# ngp-main.net
KiCad netlist of a schematic drawn in Altium Designer
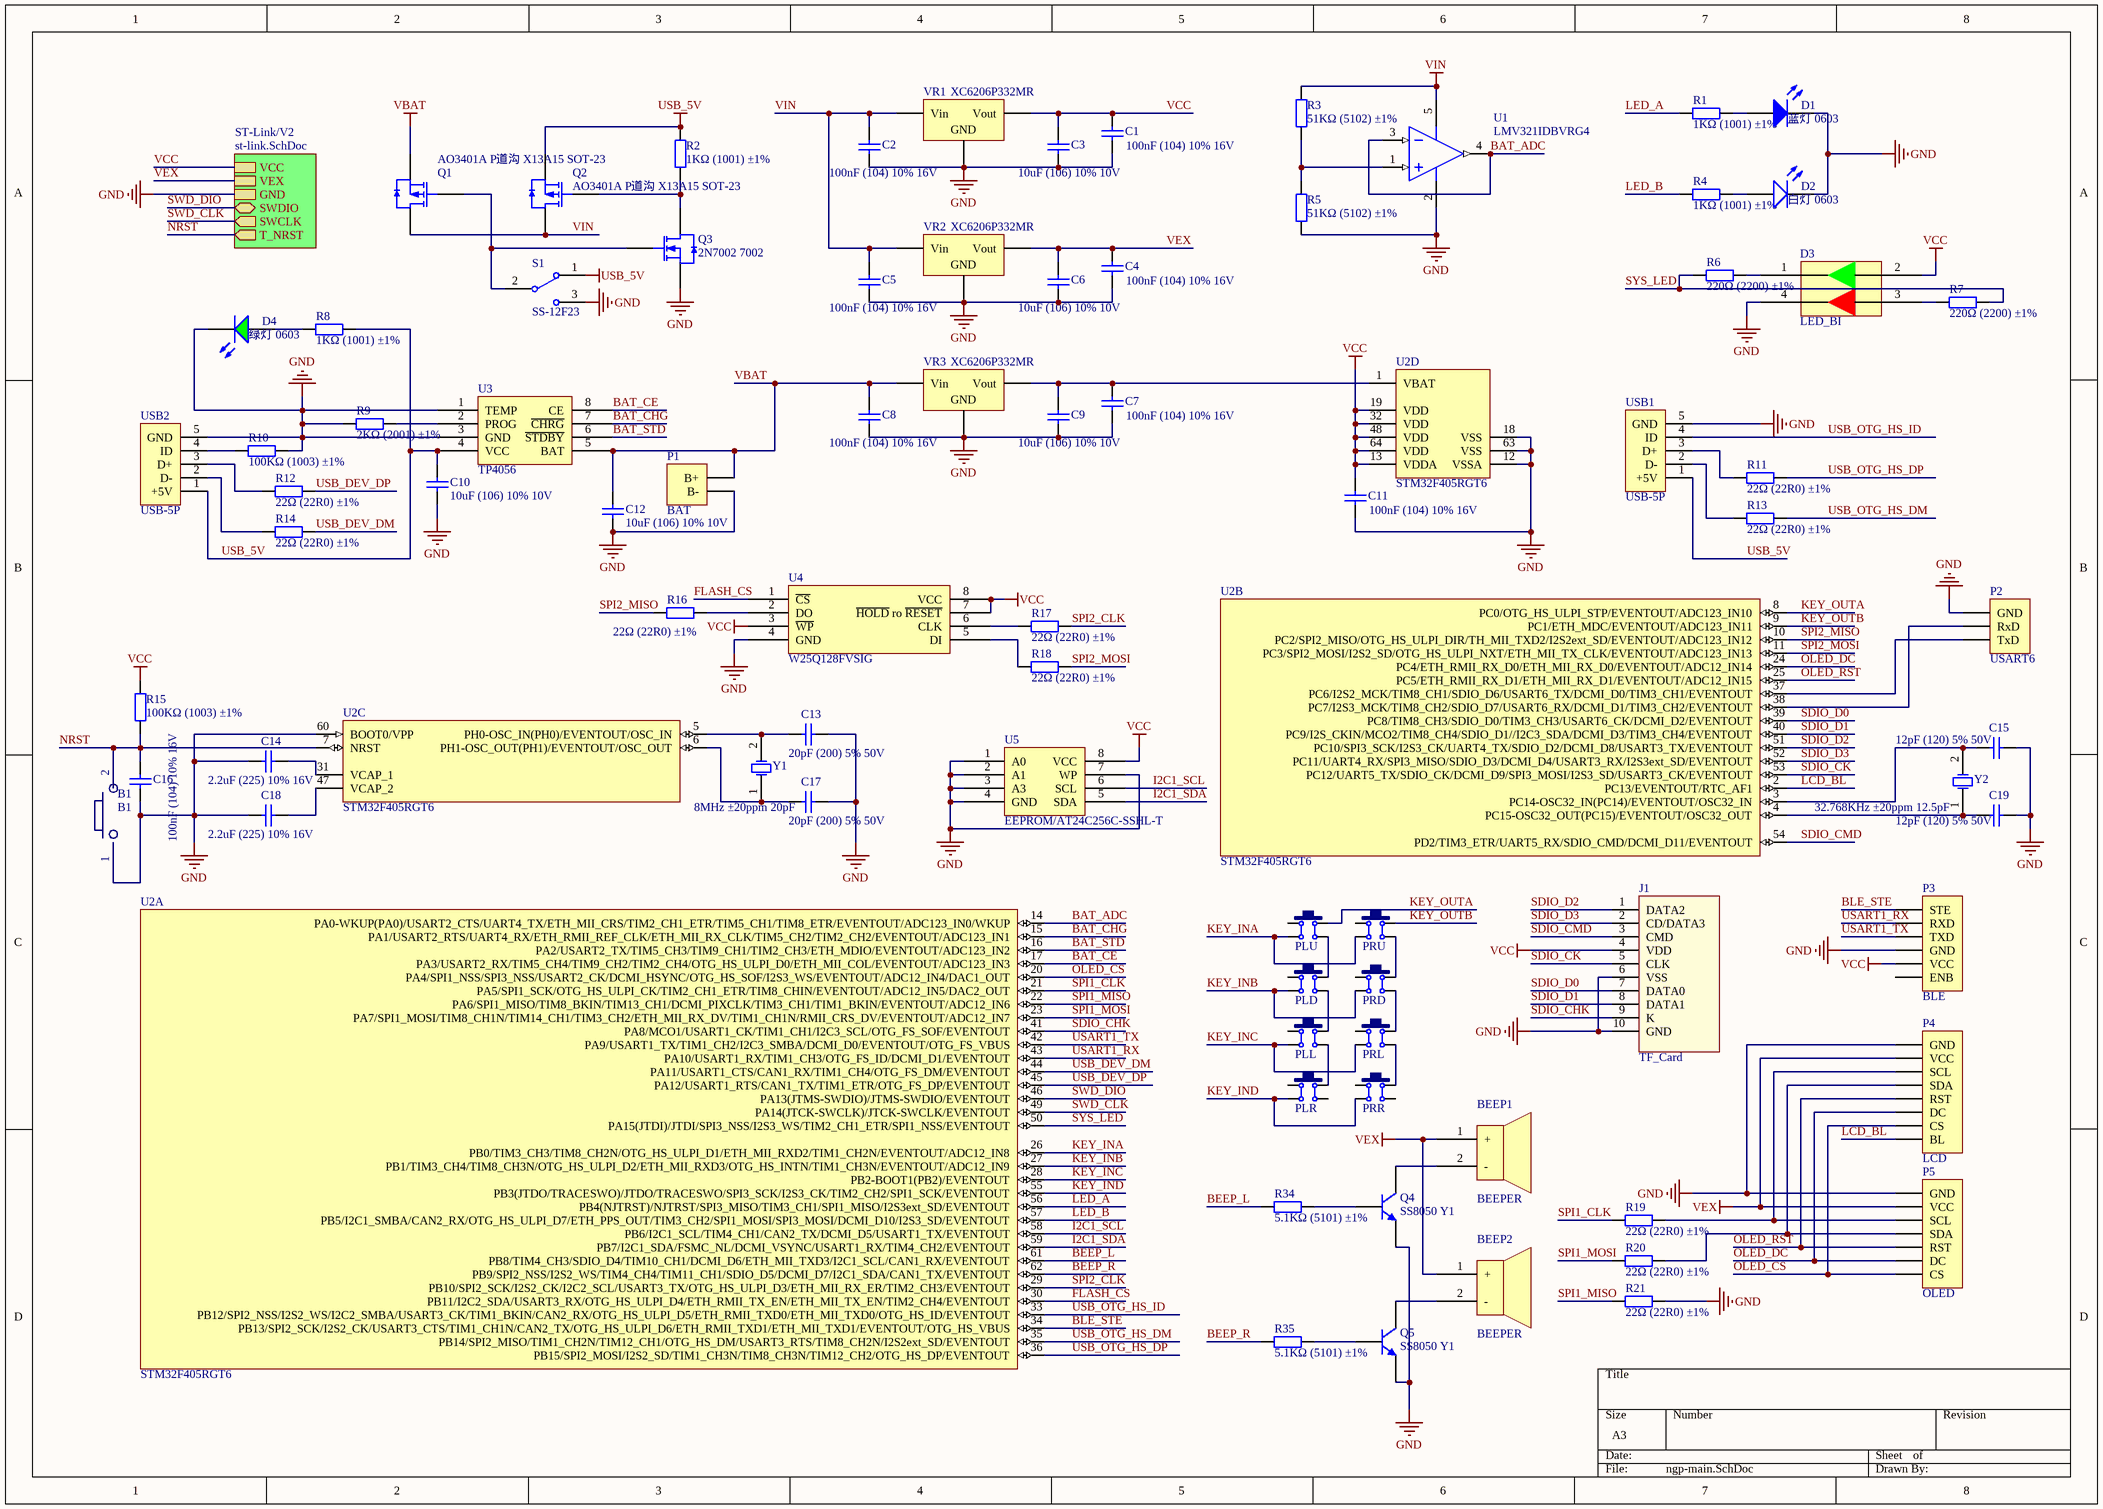
[diagram p0: ngp-main.SchDoc]

(export (version "E")
  (design (tool "Eeschema 10.0.6"))
  (components
    (comp (ref "B1")
      (value "B1")
      (footprint "MetalButton")
      (libsource (lib "MetalButton") (part "MetalButton"))
    )
    (comp (ref "BEEP1") (value "BEEPER") (footprint "BEEPER") (libsource (lib "ngv-main") (part "BEEPER")))
    (comp (ref "BEEP2") (value "BEEPER") (footprint "BEEPER") (libsource (lib "ngv-main") (part "BEEPER")))
    (comp (ref "C1")
      (value "100nF (104) 10% 16V")
      (footprint "0402_C")
      (description "贴片电容")
      (libsource (lib "Miscellaneous Devices LC") (part "0402 100nF (104) 10% 16V"))
    )
    (comp (ref "C2")
      (value "100nF (104) 10% 16V")
      (footprint "0402_C")
      (description "贴片电容")
      (libsource (lib "Miscellaneous Devices LC") (part "0402 100nF (104) 10% 16V"))
    )
    (comp (ref "C3")
      (value "10uF (106) 10% 10V")
      (footprint "0603_C")
      (description "贴片电容")
      (libsource (lib "Miscellaneous Devices LC") (part "0603 10uF (106) 10% 10V"))
    )
    (comp (ref "C4")
      (value "100nF (104) 10% 16V")
      (footprint "0402_C")
      (description "贴片电容")
      (libsource (lib "Miscellaneous Devices LC") (part "0402 100nF (104) 10% 16V"))
    )
    (comp (ref "C5")
      (value "100nF (104) 10% 16V")
      (footprint "0402_C")
      (description "贴片电容")
      (libsource (lib "Miscellaneous Devices LC") (part "0402 100nF (104) 10% 16V"))
    )
    (comp (ref "C6")
      (value "10uF (106) 10% 10V")
      (footprint "0603_C")
      (description "贴片电容")
      (libsource (lib "Miscellaneous Devices LC") (part "0603 10uF (106) 10% 10V"))
    )
    (comp (ref "C7")
      (value "100nF (104) 10% 16V")
      (footprint "0402_C")
      (description "贴片电容")
      (libsource (lib "Miscellaneous Devices LC") (part "0402 100nF (104) 10% 16V"))
    )
    (comp (ref "C8")
      (value "100nF (104) 10% 16V")
      (footprint "0402_C")
      (description "贴片电容")
      (libsource (lib "Miscellaneous Devices LC") (part "0402 100nF (104) 10% 16V"))
    )
    (comp (ref "C9")
      (value "10uF (106) 10% 10V")
      (footprint "0603_C")
      (description "贴片电容")
      (libsource (lib "Miscellaneous Devices LC") (part "0603 10uF (106) 10% 10V"))
    )
    (comp (ref "C10")
      (value "10uF (106) 10% 10V")
      (footprint "0603_C")
      (description "贴片电容")
      (libsource (lib "Miscellaneous Devices LC") (part "0603 10uF (106) 10% 10V"))
    )
    (comp (ref "C11")
      (value "100nF (104) 10% 16V")
      (footprint "0402_C")
      (description "贴片电容")
      (libsource (lib "Miscellaneous Devices LC") (part "0402 100nF (104) 10% 16V"))
    )
    (comp (ref "C12")
      (value "10uF (106) 10% 10V")
      (footprint "0603_C")
      (description "贴片电容")
      (libsource (lib "Miscellaneous Devices LC") (part "0603 10uF (106) 10% 10V"))
    )
    (comp (ref "C13")
      (value "20pF (200) 5% 50V")
      (footprint "0402_C")
      (description "贴片电容")
      (libsource (lib "Miscellaneous Devices LC") (part "0402 20pF (200) 5% 50V"))
    )
    (comp (ref "C14")
      (value "2.2uF (225) 10% 16V")
      (footprint "0603_C")
      (description "贴片电容")
      (libsource (lib "Miscellaneous Devices LC") (part "0603 2.2uF (225) 10% 16V"))
    )
    (comp (ref "C15")
      (value "12pF (120) 5% 50V")
      (footprint "0402_C")
      (description "贴片电容")
      (libsource (lib "Miscellaneous Devices LC") (part "0402 12pF (120) 5% 50V"))
    )
    (comp (ref "C16")
      (value "100nF (104) 10% 16V")
      (footprint "0402_C")
      (description "贴片电容")
      (libsource (lib "Miscellaneous Devices LC") (part "0402 100nF (104) 10% 16V"))
    )
    (comp (ref "C17")
      (value "20pF (200) 5% 50V")
      (footprint "0402_C")
      (description "贴片电容")
      (libsource (lib "Miscellaneous Devices LC") (part "0402 20pF (200) 5% 50V"))
    )
    (comp (ref "C18")
      (value "2.2uF (225) 10% 16V")
      (footprint "0603_C")
      (description "贴片电容")
      (libsource (lib "Miscellaneous Devices LC") (part "0603 2.2uF (225) 10% 16V"))
    )
    (comp (ref "C19")
      (value "12pF (120) 5% 50V")
      (footprint "0402_C")
      (description "贴片电容")
      (libsource (lib "Miscellaneous Devices LC") (part "0402 12pF (120) 5% 50V"))
    )
    (comp (ref "D1")
      (value "蓝灯 0603")
      (footprint "0603_LED_S1")
      (description "发光二极管")
      (libsource (lib "Miscellaneous Devices LC") (part "0603 蓝灯"))
    )
    (comp (ref "D2")
      (value "白灯 0603")
      (footprint "0603_LED_S1")
      (description "发光二极管")
      (libsource (lib "Miscellaneous Devices LC") (part "0603 白灯"))
    )
    (comp (ref "D3") (value "LED_BI") (footprint "LED_BI") (libsource (lib "ngv-ext") (part "LED_BI")))
    (comp (ref "D4")
      (value "绿灯 0603")
      (footprint "0603_LED_S1")
      (description "发光二极管")
      (libsource (lib "Miscellaneous Devices LC") (part "0603 绿灯"))
    )
    (comp (ref "J1")
      (value "TF_Card")
      (footprint "Micro SD")
      (description "TF卡座")
      (fields (field (name "版权归属") "源创客"))
      (libsource (lib "4.1   - 接口类") (part "TF_Card"))
    )
    (comp (ref "P1")
      (value "BAT")
      (footprint "HDR1X2")
      (description "Header, 2-Pin")
      (fields (field (name "PUBLISHER") "Altium Limited"))
      (libsource (lib "Miscellaneous Connectors") (part "Header 2"))
    )
    (comp (ref "P2")
      (value "USART6")
      (footprint "HDR1X3H")
      (description "Header, 3-Pin, Right Angle")
      (fields (field (name "PUBLISHER") "Altium Limited"))
      (libsource (lib "Miscellaneous Connectors") (part "Header 3H"))
    )
    (comp (ref "P3")
      (value "BLE")
      (footprint "HDR1X6")
      (description "Header, 6-Pin")
      (fields (field (name "PUBLISHER") "Altium Limited"))
      (libsource (lib "Miscellaneous Connectors") (part "Header 6"))
    )
    (comp (ref "P4")
      (value "LCD")
      (footprint "HDR1X8")
      (description "Header, 8-Pin")
      (fields (field (name "PUBLISHER") "Altium Limited"))
      (libsource (lib "Miscellaneous Connectors") (part "Header 8"))
    )
    (comp (ref "P5")
      (value "OLED")
      (footprint "HDR1X7")
      (description "Header, 7-Pin")
      (fields (field (name "PUBLISHER") "Altium Limited"))
      (libsource (lib "Miscellaneous Connectors") (part "Header 7"))
    )
    (comp (ref "PLD")
      (value "6x6x5")
      (footprint "TSW SMD-6*6*5")
      (description "贴片6x6轻触开关")
      (fields (field (name "版权归属") "源创客"))
      (libsource (lib "5.1   - 按键-开关") (part "TSW SMD-6x6"))
    )
    (comp (ref "PLL")
      (value "6x6x5")
      (footprint "TSW SMD-6*6*5")
      (description "贴片6x6轻触开关")
      (fields (field (name "版权归属") "源创客"))
      (libsource (lib "5.1   - 按键-开关") (part "TSW SMD-6x6"))
    )
    (comp (ref "PLR")
      (value "6x6x5")
      (footprint "TSW SMD-6*6*5")
      (description "贴片6x6轻触开关")
      (fields (field (name "版权归属") "源创客"))
      (libsource (lib "5.1   - 按键-开关") (part "TSW SMD-6x6"))
    )
    (comp (ref "PLU")
      (value "6x6x5")
      (footprint "TSW SMD-6*6*5")
      (description "贴片6x6轻触开关")
      (fields (field (name "版权归属") "源创客"))
      (libsource (lib "5.1   - 按键-开关") (part "TSW SMD-6x6"))
    )
    (comp (ref "PRD")
      (value "6x6x5")
      (footprint "TSW SMD-6*6*5")
      (description "贴片6x6轻触开关")
      (fields (field (name "版权归属") "源创客"))
      (libsource (lib "5.1   - 按键-开关") (part "TSW SMD-6x6"))
    )
    (comp (ref "PRL")
      (value "6x6x5")
      (footprint "TSW SMD-6*6*5")
      (description "贴片6x6轻触开关")
      (fields (field (name "版权归属") "源创客"))
      (libsource (lib "5.1   - 按键-开关") (part "TSW SMD-6x6"))
    )
    (comp (ref "PRR")
      (value "6x6x5")
      (footprint "TSW SMD-6*6*5")
      (description "贴片6x6轻触开关")
      (fields (field (name "版权归属") "源创客"))
      (libsource (lib "5.1   - 按键-开关") (part "TSW SMD-6x6"))
    )
    (comp (ref "PRU")
      (value "6x6x5")
      (footprint "TSW SMD-6*6*5")
      (description "贴片6x6轻触开关")
      (fields (field (name "版权归属") "源创客"))
      (libsource (lib "5.1   - 按键-开关") (part "TSW SMD-6x6"))
    )
    (comp (ref "Q1")
      (value "AO3401A P道沟 X13A15 SOT-23")
      (footprint "SOT-23-3L")
      (description "MOS(场效应管)")
      (libsource (lib "Miscellaneous Devices LC") (part "AO3401A P道沟 X13A15 SOT-23"))
    )
    (comp (ref "Q2")
      (value "AO3401A P道沟 X13A15 SOT-23")
      (footprint "SOT-23-3L")
      (description "MOS(场效应管)")
      (libsource (lib "Miscellaneous Devices LC") (part "AO3401A P道沟 X13A15 SOT-23"))
    )
    (comp (ref "Q3")
      (value "2N7002 7002")
      (footprint "SOT-23(SOT-23-3)")
      (description "MOS(场效应管)")
      (libsource (lib "Miscellaneous Devices LC") (part "2N7002 7002"))
    )
    (comp (ref "Q4")
      (value "SS8050 Y1")
      (footprint "SOT-23(SOT-23-3)")
      (description "三极管")
      (libsource (lib "Miscellaneous Devices LC") (part "SOT-23 SS8050 Y1"))
    )
    (comp (ref "Q5")
      (value "SS8050 Y1")
      (footprint "SOT-23(SOT-23-3)")
      (description "三极管")
      (libsource (lib "Miscellaneous Devices LC") (part "SOT-23 SS8050 Y1"))
    )
    (comp (ref "R1")
      (value "1KΩ (1001) ±1%")
      (footprint "0402_R")
      (description "贴片电阻")
      (libsource (lib "Miscellaneous Devices LC") (part "0402 1KΩ (1001) 1%"))
    )
    (comp (ref "R2")
      (value "1KΩ (1001) ±1%")
      (footprint "0402_R")
      (description "贴片电阻")
      (libsource (lib "") (part "0402 1KΩ (1001) 1%_1"))
    )
    (comp (ref "R3")
      (value "51KΩ (5102) ±1%")
      (footprint "0402_R")
      (description "贴片电阻")
      (libsource (lib "Miscellaneous Devices LC") (part "0402 51KΩ (5102) 1%"))
    )
    (comp (ref "R4")
      (value "1KΩ (1001) ±1%")
      (footprint "0402_R")
      (description "贴片电阻")
      (libsource (lib "Miscellaneous Devices LC") (part "0402 1KΩ (1001) 1%"))
    )
    (comp (ref "R5")
      (value "51KΩ (5102) ±1%")
      (footprint "0402_R")
      (description "贴片电阻")
      (libsource (lib "Miscellaneous Devices LC") (part "0402 51KΩ (5102) 1%"))
    )
    (comp (ref "R6")
      (value "220Ω (2200) ±1%")
      (footprint "0402_R")
      (description "贴片电阻")
      (libsource (lib "Miscellaneous Devices LC") (part "0402 220Ω (2200) 1%"))
    )
    (comp (ref "R7")
      (value "220Ω (2200) ±1%")
      (footprint "0402_R")
      (description "贴片电阻")
      (libsource (lib "Miscellaneous Devices LC") (part "0402 220Ω (2200) 1%"))
    )
    (comp (ref "R8")
      (value "1KΩ (1001) ±1%")
      (footprint "0402_R")
      (description "贴片电阻")
      (libsource (lib "Miscellaneous Devices LC") (part "0402 1KΩ (1001) 1%"))
    )
    (comp (ref "R9")
      (value "2KΩ (2001) ±1%")
      (footprint "0402_R")
      (description "贴片电阻")
      (libsource (lib "Miscellaneous Devices LC") (part "0402 2KΩ (2001) 1%"))
    )
    (comp (ref "R10")
      (value "100KΩ (1003) ±1%")
      (footprint "0402_R")
      (description "贴片电阻")
      (libsource (lib "Miscellaneous Devices LC") (part "0402 100KΩ (1003) 1%"))
    )
    (comp (ref "R11")
      (value "22Ω (22R0) ±1%")
      (footprint "0402_R")
      (description "贴片电阻")
      (libsource (lib "Miscellaneous Devices LC") (part "0402 22Ω (22R0) 1%"))
    )
    (comp (ref "R12")
      (value "22Ω (22R0) ±1%")
      (footprint "0402_R")
      (description "贴片电阻")
      (libsource (lib "Miscellaneous Devices LC") (part "0402 22Ω (22R0) 1%"))
    )
    (comp (ref "R13")
      (value "22Ω (22R0) ±1%")
      (footprint "0402_R")
      (description "贴片电阻")
      (libsource (lib "Miscellaneous Devices LC") (part "0402 22Ω (22R0) 1%"))
    )
    (comp (ref "R14")
      (value "22Ω (22R0) ±1%")
      (footprint "0402_R")
      (description "贴片电阻")
      (libsource (lib "Miscellaneous Devices LC") (part "0402 22Ω (22R0) 1%"))
    )
    (comp (ref "R15")
      (value "100KΩ (1003) ±1%")
      (footprint "0402_R")
      (description "贴片电阻")
      (libsource (lib "") (part "0402 100KΩ (1003) 1%_1"))
    )
    (comp (ref "R16")
      (value "22Ω (22R0) ±1%")
      (footprint "0402_R")
      (description "贴片电阻")
      (libsource (lib "Miscellaneous Devices LC") (part "0402 22Ω (22R0) 1%"))
    )
    (comp (ref "R17")
      (value "22Ω (22R0) ±1%")
      (footprint "0402_R")
      (description "贴片电阻")
      (libsource (lib "Miscellaneous Devices LC") (part "0402 22Ω (22R0) 1%"))
    )
    (comp (ref "R18")
      (value "22Ω (22R0) ±1%")
      (footprint "0402_R")
      (description "贴片电阻")
      (libsource (lib "Miscellaneous Devices LC") (part "0402 22Ω (22R0) 1%"))
    )
    (comp (ref "R19")
      (value "22Ω (22R0) ±1%")
      (footprint "0402_R")
      (description "贴片电阻")
      (libsource (lib "Miscellaneous Devices LC") (part "0402 22Ω (22R0) 1%"))
    )
    (comp (ref "R20")
      (value "22Ω (22R0) ±1%")
      (footprint "0402_R")
      (description "贴片电阻")
      (libsource (lib "Miscellaneous Devices LC") (part "0402 22Ω (22R0) 1%"))
    )
    (comp (ref "R21")
      (value "22Ω (22R0) ±1%")
      (footprint "0402_R")
      (description "贴片电阻")
      (libsource (lib "Miscellaneous Devices LC") (part "0402 22Ω (22R0) 1%"))
    )
    (comp (ref "R34")
      (value "5.1KΩ (5101) ±1%")
      (footprint "0402_R")
      (description "贴片电阻")
      (libsource (lib "Miscellaneous Devices LC") (part "0402 5.1KΩ (5101) 1%"))
    )
    (comp (ref "R35")
      (value "5.1KΩ (5101) ±1%")
      (footprint "0402_R")
      (description "贴片电阻")
      (libsource (lib "Miscellaneous Devices LC") (part "0402 5.1KΩ (5101) 1%"))
    )
    (comp (ref "S1")
      (value "SS-12F23")
      (footprint "MSK-12C01-07")
      (description "1路波动开关")
      (fields (field (name "版权归属") "源创客"))
      (libsource (lib "5.1   - 按键-开关") (part "SSW-1P"))
    )
    (comp (ref "U1")
      (value "LMV321IDBVRG4")
      (footprint "SOT-23-5")
      (description "运放")
      (libsource (lib "Miscellaneous Devices LC") (part "LMV321IDBVRG4_[C7972]"))
    )
    (comp (ref "U2")
      (value "STM32F405RGT6")
      (footprint "LQFP-64_10x10x05P")
      (description "ARM")
      (libsource (lib "Miscellaneous Devices LC") (part "STM32F405RGT6"))
    )
    (comp (ref "U3")
      (value "TP4056")
      (footprint "SOP-8_EP_150mil")
      (description "电池电源管理")
      (libsource (lib "Miscellaneous Devices LC") (part "TP4056_[C16581]"))
    )
    (comp (ref "U4")
      (value "W25Q128FVSIG")
      (footprint "SOIC-8_208mil")
      (description "Flash ROM")
      (libsource (lib "Miscellaneous Devices LC") (part "W25Q128FVSIG_[C35101]"))
    )
    (comp (ref "U5")
      (value "EEPROM/AT24C256C-SSHL-T")
      (footprint "SOIC-8_150mil")
      (description "EEPROM")
      (libsource (lib "Miscellaneous Devices LC") (part "EEPROM/AT24C256C-SSHL-T_[C6482]"))
    )
    (comp (ref "USB1")
      (value "USB-5P")
      (footprint "USB-MICRO_D")
      (description "微型USB母座")
      (fields (field (name "版权归属") "源创客"))
      (libsource (lib "4.1   - 接口类") (part "USB-5P"))
    )
    (comp (ref "USB2")
      (value "USB-5P")
      (footprint "USB-MICRO_D")
      (description "微型USB母座")
      (fields (field (name "版权归属") "源创客"))
      (libsource (lib "4.1   - 接口类") (part "USB-5P"))
    )
    (comp (ref "VR1")
      (value "XC6206P332MR")
      (footprint "SOT-23-3L")
      (description "低压差线性稳压(LDO)")
      (libsource (lib "Miscellaneous Devices LC") (part "SOT-23 XC6206P332MR"))
    )
    (comp (ref "VR2")
      (value "XC6206P332MR")
      (footprint "SOT-23-3L")
      (description "低压差线性稳压(LDO)")
      (libsource (lib "Miscellaneous Devices LC") (part "SOT-23 XC6206P332MR"))
    )
    (comp (ref "VR3")
      (value "XC6206P332MR")
      (footprint "SOT-23-3L")
      (description "低压差线性稳压(LDO)")
      (libsource (lib "Miscellaneous Devices LC") (part "SOT-23 XC6206P332MR"))
    )
    (comp (ref "Y1")
      (value "8MHz ±20ppm 20pF")
      (footprint "SMD-5032_2P")
      (description "贴片晶振")
      (libsource (lib "Miscellaneous Devices LC") (part "SMD-5032_2P 8MHz 20ppm 20pF"))
    )
    (comp (ref "Y2")
      (value "32.768KHz ±20ppm 12.5pF")
      (footprint "SMD-3215_2P FC - 135")
      (description "贴片晶振")
      (libsource (lib "Miscellaneous Devices LC") (part "SMD-3215_2P 32.768KHz 20ppm 12.5pF"))
    )
  )
  (nets
    (net (code "1") (name "/BAT_ADC") (class "Default")
      (node (ref "U1") (pin "3") (pinfunction "IN-_3") (pintype "input"))
      (node (ref "U1") (pin "4") (pinfunction "OUT_4") (pintype "output"))
      (node (ref "U2") (pin "14") (pinfunction "PA0-WKUP(PA0)/USART2_CTS/UART4_TX/ETH_MII_CRS/TIM2_CH1_ETR/TIM5_CH1/TIM8_ETR/EVENTOUT/ADC123_IN0/WKUP_14") (pintype "bidirectional"))
    )
    (net (code "2") (name "/BAT_CE") (class "Default")
      (node (ref "U2") (pin "17") (pinfunction "PA3/USART2_RX/TIM5_CH4/TIM9_CH2/TIM2_CH4/OTG_HS_ULPI_D0/ETH_MII_COL/EVENTOUT/ADC123_IN3_17") (pintype "bidirectional"))
      (node (ref "U3") (pin "8") (pinfunction "CE_8") (pintype "passive"))
    )
    (net (code "3") (name "/BAT_CHG") (class "Default")
      (node (ref "U2") (pin "15") (pinfunction "PA1/USART2_RTS/UART4_RX/ETH_RMII_REF_CLK/ETH_MII_RX_CLK/TIM5_CH2/TIM2_CH2/EVENTOUT/ADC123_IN1_15") (pintype "bidirectional"))
      (node (ref "U3") (pin "7") (pinfunction "~{CHRG}_7") (pintype "passive"))
    )
    (net (code "4") (name "/BAT_STD") (class "Default")
      (node (ref "U2") (pin "16") (pinfunction "PA2/USART2_TX/TIM5_CH3/TIM9_CH1/TIM2_CH3/ETH_MDIO/EVENTOUT/ADC123_IN2_16") (pintype "bidirectional"))
      (node (ref "U3") (pin "6") (pinfunction "~{STDBY}_6") (pintype "passive"))
    )
    (net (code "5") (name "/BEEP_L") (class "Default")
      (node (ref "R34") (pin "1") (pinfunction "1_1") (pintype "passive"))
      (node (ref "U2") (pin "61") (pinfunction "PB8/TIM4_CH3/SDIO_D4/TIM10_CH1/DCMI_D6/ETH_MII_TXD3/I2C1_SCL/CAN1_RX/EVENTOUT_61") (pintype "bidirectional"))
    )
    (net (code "6") (name "/BEEP_R") (class "Default")
      (node (ref "R35") (pin "1") (pinfunction "1_1") (pintype "passive"))
      (node (ref "U2") (pin "62") (pinfunction "PB9/SPI2_NSS/I2S2_WS/TIM4_CH4/TIM11_CH1/SDIO_D5/DCMI_D7/I2C1_SDA/CAN1_TX/EVENTOUT_62") (pintype "bidirectional"))
    )
    (net (code "7") (name "/BLE_STE") (class "Default")
      (node (ref "P3") (pin "1") (pinfunction "STE_1") (pintype "passive"))
      (node (ref "U2") (pin "34") (pinfunction "PB13/SPI2_SCK/I2S2_CK/USART3_CTS/TIM1_CH1N/CAN2_TX/OTG_HS_ULPI_D6/ETH_RMII_TXD1/ETH_MII_TXD1/EVENTOUT/OTG_HS_VBUS_34") (pintype "bidirectional"))
    )
    (net (code "8") (name "/FLASH_CS") (class "Default")
      (node (ref "U2") (pin "30") (pinfunction "PB11/I2C2_SDA/USART3_RX/OTG_HS_ULPI_D4/ETH_RMII_TX_EN/ETH_MII_TX_EN/TIM2_CH4/EVENTOUT_30") (pintype "bidirectional"))
      (node (ref "U4") (pin "1") (pinfunction "~{CS}_1") (pintype "passive"))
    )
    (net (code "9") (name "/I2C1_SCL") (class "Default")
      (node (ref "U2") (pin "58") (pinfunction "PB6/I2C1_SCL/TIM4_CH1/CAN2_TX/DCMI_D5/USART1_TX/EVENTOUT_58") (pintype "bidirectional"))
      (node (ref "U5") (pin "6") (pinfunction "SCL_6") (pintype "passive"))
    )
    (net (code "10") (name "/I2C1_SDA") (class "Default")
      (node (ref "U2") (pin "59") (pinfunction "PB7/I2C1_SDA/FSMC_NL/DCMI_VSYNC/USART1_RX/TIM4_CH2/EVENTOUT_59") (pintype "bidirectional"))
      (node (ref "U5") (pin "5") (pinfunction "SDA_5") (pintype "passive"))
    )
    (net (code "11") (name "/KEY_INA") (class "Default")
      (node (ref "PLU") (pin "4") (pinfunction "4_4") (pintype "passive"))
      (node (ref "PRU") (pin "4") (pinfunction "4_4") (pintype "passive"))
      (node (ref "U2") (pin "26") (pinfunction "PB0/TIM3_CH3/TIM8_CH2N/OTG_HS_ULPI_D1/ETH_MII_RXD2/TIM1_CH2N/EVENTOUT/ADC12_IN8_26") (pintype "bidirectional"))
    )
    (net (code "12") (name "/KEY_INB") (class "Default")
      (node (ref "PLD") (pin "4") (pinfunction "4_4") (pintype "passive"))
      (node (ref "PRD") (pin "4") (pinfunction "4_4") (pintype "passive"))
      (node (ref "U2") (pin "27") (pinfunction "PB1/TIM3_CH4/TIM8_CH3N/OTG_HS_ULPI_D2/ETH_MII_RXD3/OTG_HS_INTN/TIM1_CH3N/EVENTOUT/ADC12_IN9_27") (pintype "bidirectional"))
    )
    (net (code "13") (name "/KEY_INC") (class "Default")
      (node (ref "PLL") (pin "4") (pinfunction "4_4") (pintype "passive"))
      (node (ref "PRL") (pin "4") (pinfunction "4_4") (pintype "passive"))
      (node (ref "U2") (pin "28") (pinfunction "PB2-BOOT1(PB2)/EVENTOUT_28") (pintype "bidirectional"))
    )
    (net (code "14") (name "/KEY_IND") (class "Default")
      (node (ref "PLR") (pin "4") (pinfunction "4_4") (pintype "passive"))
      (node (ref "PRR") (pin "4") (pinfunction "4_4") (pintype "passive"))
      (node (ref "U2") (pin "55") (pinfunction "PB3(JTDO/TRACESWO)/JTDO/TRACESWO/SPI3_SCK/I2S3_CK/TIM2_CH2/SPI1_SCK/EVENTOUT_55") (pintype "bidirectional"))
    )
    (net (code "15") (name "/KEY_OUTA") (class "Default")
      (node (ref "PLU") (pin "2") (pinfunction "2_2") (pintype "passive"))
      (node (ref "U2") (pin "8") (pinfunction "PC0/OTG_HS_ULPI_STP/EVENTOUT/ADC123_IN10_8") (pintype "bidirectional"))
    )
    (net (code "16") (name "/KEY_OUTB") (class "Default")
      (node (ref "PRU") (pin "2") (pinfunction "2_2") (pintype "passive"))
      (node (ref "U2") (pin "9") (pinfunction "PC1/ETH_MDC/EVENTOUT/ADC123_IN11_9") (pintype "bidirectional"))
    )
    (net (code "17") (name "/LCD_BL") (class "Default")
      (node (ref "P4") (pin "8") (pinfunction "BL_8") (pintype "passive"))
      (node (ref "U2") (pin "2") (pinfunction "PC13/EVENTOUT/RTC_AF1_2") (pintype "bidirectional"))
    )
    (net (code "18") (name "/LED_A") (class "Default")
      (node (ref "R1") (pin "2") (pinfunction "2_2") (pintype "passive"))
      (node (ref "U2") (pin "56") (pinfunction "PB4(NJTRST)/NJTRST/SPI3_MISO/TIM3_CH1/SPI1_MISO/I2S3ext_SD/EVENTOUT_56") (pintype "bidirectional"))
    )
    (net (code "19") (name "/LED_B") (class "Default")
      (node (ref "R4") (pin "2") (pinfunction "2_2") (pintype "passive"))
      (node (ref "U2") (pin "57") (pinfunction "PB5/I2C1_SMBA/CAN2_RX/OTG_HS_ULPI_D7/ETH_PPS_OUT/TIM3_CH2/SPI1_MOSI/SPI3_MOSI/DCMI_D10/I2S3_SD/EVENTOUT_57") (pintype "bidirectional"))
    )
    (net (code "20") (name "/NRST") (class "Default")
      (node (ref "B1") (pin "2") (pinfunction "2_2") (pintype "passive"))
      (node (ref "C16") (pin "2") (pinfunction "2_2") (pintype "passive"))
      (node (ref "R15") (pin "1") (pinfunction "1_1") (pintype "passive"))
      (node (ref "U2") (pin "7") (pinfunction "NRST_7") (pintype "bidirectional"))
    )
    (net (code "21") (name "/OLED_CS") (class "Default")
      (node (ref "P4") (pin "7") (pinfunction "CS_7") (pintype "passive"))
      (node (ref "P5") (pin "7") (pinfunction "CS_7") (pintype "passive"))
      (node (ref "U2") (pin "20") (pinfunction "PA4/SPI1_NSS/SPI3_NSS/USART2_CK/DCMI_HSYNC/OTG_HS_SOF/I2S3_WS/EVENTOUT/ADC12_IN4/DAC1_OUT_20") (pintype "bidirectional"))
    )
    (net (code "22") (name "/OLED_DC") (class "Default")
      (node (ref "P4") (pin "6") (pinfunction "DC_6") (pintype "passive"))
      (node (ref "P5") (pin "6") (pinfunction "DC_6") (pintype "passive"))
      (node (ref "U2") (pin "24") (pinfunction "PC4/ETH_RMII_RX_D0/ETH_MII_RX_D0/EVENTOUT/ADC12_IN14_24") (pintype "bidirectional"))
    )
    (net (code "23") (name "/OLED_RST") (class "Default")
      (node (ref "P4") (pin "5") (pinfunction "RST_5") (pintype "passive"))
      (node (ref "P5") (pin "5") (pinfunction "RST_5") (pintype "passive"))
      (node (ref "U2") (pin "25") (pinfunction "PC5/ETH_RMII_RX_D1/ETH_MII_RX_D1/EVENTOUT/ADC12_IN15_25") (pintype "bidirectional"))
    )
    (net (code "24") (name "/SDIO_CHK") (class "Default")
      (node (ref "J1") (pin "9") (pinfunction "K_9") (pintype "passive"))
      (node (ref "U2") (pin "41") (pinfunction "PA8/MCO1/USART1_CK/TIM1_CH1/I2C3_SCL/OTG_FS_SOF/EVENTOUT_41") (pintype "bidirectional"))
    )
    (net (code "25") (name "/SDIO_CK") (class "Default")
      (node (ref "J1") (pin "5") (pinfunction "CLK_5") (pintype "passive"))
      (node (ref "U2") (pin "53") (pinfunction "PC12/UART5_TX/SDIO_CK/DCMI_D9/SPI3_MOSI/I2S3_SD/USART3_CK/EVENTOUT_53") (pintype "bidirectional"))
    )
    (net (code "26") (name "/SDIO_CMD") (class "Default")
      (node (ref "J1") (pin "3") (pinfunction "CMD_3") (pintype "passive"))
      (node (ref "U2") (pin "54") (pinfunction "PD2/TIM3_ETR/UART5_RX/SDIO_CMD/DCMI_D11/EVENTOUT_54") (pintype "bidirectional"))
    )
    (net (code "27") (name "/SDIO_D0") (class "Default")
      (node (ref "J1") (pin "7") (pinfunction "DATA0_7") (pintype "passive"))
      (node (ref "U2") (pin "39") (pinfunction "PC8/TIM8_CH3/SDIO_D0/TIM3_CH3/USART6_CK/DCMI_D2/EVENTOUT_39") (pintype "bidirectional"))
    )
    (net (code "28") (name "/SDIO_D1") (class "Default")
      (node (ref "J1") (pin "8") (pinfunction "DATA1_8") (pintype "passive"))
      (node (ref "U2") (pin "40") (pinfunction "PC9/I2S_CKIN/MCO2/TIM8_CH4/SDIO_D1//I2C3_SDA/DCMI_D3/TIM3_CH4/EVENTOUT_40") (pintype "bidirectional"))
    )
    (net (code "29") (name "/SDIO_D2") (class "Default")
      (node (ref "J1") (pin "1") (pinfunction "DATA2_1") (pintype "passive"))
      (node (ref "U2") (pin "51") (pinfunction "PC10/SPI3_SCK/I2S3_CK/UART4_TX/SDIO_D2/DCMI_D8/USART3_TX/EVENTOUT_51") (pintype "bidirectional"))
    )
    (net (code "30") (name "/SDIO_D3") (class "Default")
      (node (ref "J1") (pin "2") (pinfunction "CD/DATA3_2") (pintype "passive"))
      (node (ref "U2") (pin "52") (pinfunction "PC11/UART4_RX/SPI3_MISO/SDIO_D3/DCMI_D4/USART3_RX/I2S3ext_SD/EVENTOUT_52") (pintype "bidirectional"))
    )
    (net (code "31") (name "/SPI1_CLK") (class "Default")
      (node (ref "R19") (pin "1") (pinfunction "1_1") (pintype "passive"))
      (node (ref "U2") (pin "21") (pinfunction "PA5/SPI1_SCK/OTG_HS_ULPI_CK/TIM2_CH1_ETR/TIM8_CHIN/EVENTOUT/ADC12_IN5/DAC2_OUT_21") (pintype "bidirectional"))
    )
    (net (code "32") (name "/SPI1_MISO") (class "Default")
      (node (ref "R21") (pin "1") (pinfunction "1_1") (pintype "passive"))
      (node (ref "U2") (pin "22") (pinfunction "PA6/SPI1_MISO/TIM8_BKIN/TIM13_CH1/DCMI_PIXCLK/TIM3_CH1/TIM1_BKIN/EVENTOUT/ADC12_IN6_22") (pintype "bidirectional"))
    )
    (net (code "33") (name "/SPI1_MOSI") (class "Default")
      (node (ref "R20") (pin "1") (pinfunction "1_1") (pintype "passive"))
      (node (ref "U2") (pin "23") (pinfunction "PA7/SPI1_MOSI/TIM8_CH1N/TIM14_CH1/TIM3_CH2/ETH_MII_RX_DV/TIM1_CH1N/RMII_CRS_DV/EVENTOUT/ADC12_IN7_23") (pintype "bidirectional"))
    )
    (net (code "34") (name "/SPI2_CLK") (class "Default")
      (node (ref "R17") (pin "2") (pinfunction "2_2") (pintype "passive"))
      (node (ref "U2") (pin "29") (pinfunction "PB10/SPI2_SCK/I2S2_CK/I2C2_SCL/USART3_TX/OTG_HS_ULPI_D3/ETH_MII_RX_ER/TIM2_CH3/EVENTOUT_29") (pintype "bidirectional"))
    )
    (net (code "35") (name "/SPI2_MISO") (class "Default")
      (node (ref "R16") (pin "1") (pinfunction "1_1") (pintype "passive"))
      (node (ref "U2") (pin "10") (pinfunction "PC2/SPI2_MISO/OTG_HS_ULPI_DIR/TH_MII_TXD2/I2S2ext_SD/EVENTOUT/ADC123_IN12_10") (pintype "bidirectional"))
    )
    (net (code "36") (name "/SPI2_MOSI") (class "Default")
      (node (ref "R18") (pin "2") (pinfunction "2_2") (pintype "passive"))
      (node (ref "U2") (pin "11") (pinfunction "PC3/SPI2_MOSI/I2S2_SD/OTG_HS_ULPI_NXT/ETH_MII_TX_CLK/EVENTOUT/ADC123_IN13_11") (pintype "bidirectional"))
    )
    (net (code "37") (name "/SWD_CLK") (class "Default")
      (node (ref "U2") (pin "49") (pinfunction "PA14(JTCK-SWCLK)/JTCK-SWCLK/EVENTOUT_49") (pintype "bidirectional"))
    )
    (net (code "38") (name "/SWD_DIO") (class "Default")
      (node (ref "U2") (pin "46") (pinfunction "PA13(JTMS-SWDIO)/JTMS-SWDIO/EVENTOUT_46") (pintype "bidirectional"))
    )
    (net (code "39") (name "/SYS_LED") (class "Default")
      (node (ref "R6") (pin "1") (pinfunction "1_1") (pintype "passive"))
      (node (ref "R7") (pin "2") (pinfunction "2_2") (pintype "passive"))
      (node (ref "U2") (pin "50") (pinfunction "PA15(JTDI)/JTDI/SPI3_NSS/I2S3_WS/TIM2_CH1_ETR/SPI1_NSS/EVENTOUT_50") (pintype "bidirectional"))
    )
    (net (code "40") (name "/USART1_RX") (class "Default")
      (node (ref "P3") (pin "2") (pinfunction "RXD_2") (pintype "passive"))
      (node (ref "U2") (pin "43") (pinfunction "PA10/USART1_RX/TIM1_CH3/OTG_FS_ID/DCMI_D1/EVENTOUT_43") (pintype "bidirectional"))
    )
    (net (code "41") (name "/USART1_TX") (class "Default")
      (node (ref "P3") (pin "3") (pinfunction "TXD_3") (pintype "passive"))
      (node (ref "U2") (pin "42") (pinfunction "PA9/USART1_TX/TIM1_CH2/I2C3_SMBA/DCMI_D0/EVENTOUT/OTG_FS_VBUS_42") (pintype "bidirectional"))
    )
    (net (code "42") (name "/USB_DEV_DM") (class "Default")
      (node (ref "R14") (pin "2") (pinfunction "2_2") (pintype "passive"))
      (node (ref "U2") (pin "44") (pinfunction "PA11/USART1_CTS/CAN1_RX/TIM1_CH4/OTG_FS_DM/EVENTOUT_44") (pintype "bidirectional"))
    )
    (net (code "43") (name "/USB_DEV_DP") (class "Default")
      (node (ref "R12") (pin "2") (pinfunction "2_2") (pintype "passive"))
      (node (ref "U2") (pin "45") (pinfunction "PA12/USART1_RTS/CAN1_TX/TIM1_ETR/OTG_FS_DP/EVENTOUT_45") (pintype "bidirectional"))
    )
    (net (code "44") (name "/USB_OTG_HS_DM") (class "Default")
      (node (ref "R13") (pin "2") (pinfunction "2_2") (pintype "passive"))
      (node (ref "U2") (pin "35") (pinfunction "PB14/SPI2_MISO/TIM1_CH2N/TIM12_CH1/OTG_HS_DM/USART3_RTS/TIM8_CH2N/I2S2ext_SD/EVENTOUT_35") (pintype "bidirectional"))
    )
    (net (code "45") (name "/USB_OTG_HS_DP") (class "Default")
      (node (ref "R11") (pin "2") (pinfunction "2_2") (pintype "passive"))
      (node (ref "U2") (pin "36") (pinfunction "PB15/SPI2_MOSI/I2S2_SD/TIM1_CH3N/TIM8_CH3N/TIM12_CH2/OTG_HS_DP/EVENTOUT_36") (pintype "bidirectional"))
    )
    (net (code "46") (name "/USB_OTG_HS_ID") (class "Default")
      (node (ref "U2") (pin "33") (pinfunction "PB12/SPI2_NSS/I2S2_WS/I2C2_SMBA/USART3_CK/TIM1_BKIN/CAN2_RX/OTG_HS_ULPI_D5/ETH_RMII_TXD0/ETH_MII_TXD0/OTG_HS_ID/EVENTOUT_33") (pintype "bidirectional"))
      (node (ref "USB1") (pin "4") (pinfunction "ID_4") (pintype "passive"))
    )
    (net (code "47") (name "GND") (class "Default")
      (node (ref "B1") (pin "1") (pinfunction "1_1") (pintype "passive"))
      (node (ref "C1") (pin "1") (pinfunction "1_1") (pintype "passive"))
      (node (ref "C10") (pin "1") (pinfunction "1_1") (pintype "passive"))
      (node (ref "C11") (pin "1") (pinfunction "1_1") (pintype "passive"))
      (node (ref "C12") (pin "2") (pinfunction "2_2") (pintype "passive"))
      (node (ref "C13") (pin "2") (pinfunction "2_2") (pintype "passive"))
      (node (ref "C14") (pin "1") (pinfunction "1_1") (pintype "passive"))
      (node (ref "C15") (pin "2") (pinfunction "2_2") (pintype "passive"))
      (node (ref "C16") (pin "1") (pinfunction "1_1") (pintype "passive"))
      (node (ref "C17") (pin "2") (pinfunction "2_2") (pintype "passive"))
      (node (ref "C18") (pin "1") (pinfunction "1_1") (pintype "passive"))
      (node (ref "C19") (pin "2") (pinfunction "2_2") (pintype "passive"))
      (node (ref "C2") (pin "1") (pinfunction "1_1") (pintype "passive"))
      (node (ref "C3") (pin "2") (pinfunction "2_2") (pintype "passive"))
      (node (ref "C4") (pin "1") (pinfunction "1_1") (pintype "passive"))
      (node (ref "C5") (pin "1") (pinfunction "1_1") (pintype "passive"))
      (node (ref "C6") (pin "2") (pinfunction "2_2") (pintype "passive"))
      (node (ref "C7") (pin "1") (pinfunction "1_1") (pintype "passive"))
      (node (ref "C8") (pin "1") (pinfunction "1_1") (pintype "passive"))
      (node (ref "C9") (pin "2") (pinfunction "2_2") (pintype "passive"))
      (node (ref "D1") (pin "K") (pinfunction "K_K") (pintype "passive"))
      (node (ref "D2") (pin "K") (pinfunction "K_K") (pintype "passive"))
      (node (ref "D3") (pin "4") (pinfunction "4_4") (pintype "passive"))
      (node (ref "D4") (pin "K") (pinfunction "K_K") (pintype "passive"))
      (node (ref "J1") (pin "10") (pinfunction "GND_10") (pintype "passive"))
      (node (ref "J1") (pin "6") (pinfunction "VSS_6") (pintype "passive"))
      (node (ref "P1") (pin "1") (pinfunction "B-_1") (pintype "passive"))
      (node (ref "P2") (pin "1") (pinfunction "GND_1") (pintype "passive"))
      (node (ref "P3") (pin "4") (pinfunction "GND_4") (pintype "passive"))
      (node (ref "P4") (pin "1") (pinfunction "GND_1") (pintype "passive"))
      (node (ref "P5") (pin "1") (pinfunction "GND_1") (pintype "passive"))
      (node (ref "Q3") (pin "2") (pinfunction "S_2") (pintype "passive"))
      (node (ref "Q4") (pin "2") (pinfunction "E_2") (pintype "passive"))
      (node (ref "Q5") (pin "2") (pinfunction "E_2") (pintype "passive"))
      (node (ref "R10") (pin "2") (pinfunction "2_2") (pintype "passive"))
      (node (ref "R21") (pin "2") (pinfunction "2_2") (pintype "passive"))
      (node (ref "R5") (pin "1") (pinfunction "1_1") (pintype "passive"))
      (node (ref "R9") (pin "1") (pinfunction "1_1") (pintype "passive"))
      (node (ref "S1") (pin "3") (pinfunction "3_3") (pintype "passive"))
      (node (ref "U1") (pin "2") (pinfunction "V-_2") (pintype "power_in"))
      (node (ref "U2") (pin "12") (pinfunction "VSSA_12") (pintype "power_in"))
      (node (ref "U2") (pin "18") (pinfunction "VSS_18") (pintype "power_in"))
      (node (ref "U2") (pin "60") (pinfunction "BOOT0/VPP_60") (pintype "input"))
      (node (ref "U2") (pin "63") (pinfunction "VSS_63") (pintype "power_in"))
      (node (ref "U3") (pin "1") (pinfunction "TEMP_1") (pintype "passive"))
      (node (ref "U3") (pin "3") (pinfunction "GND_3") (pintype "passive"))
      (node (ref "U4") (pin "4") (pinfunction "GND_4") (pintype "passive"))
      (node (ref "U5") (pin "1") (pinfunction "A0_1") (pintype "passive"))
      (node (ref "U5") (pin "2") (pinfunction "A1_2") (pintype "passive"))
      (node (ref "U5") (pin "3") (pinfunction "A3_3") (pintype "passive"))
      (node (ref "U5") (pin "4") (pinfunction "GND_4") (pintype "passive"))
      (node (ref "U5") (pin "7") (pinfunction "WP_7") (pintype "passive"))
      (node (ref "USB1") (pin "5") (pinfunction "GND_5") (pintype "passive"))
      (node (ref "USB2") (pin "5") (pinfunction "GND_5") (pintype "passive"))
      (node (ref "VR1") (pin "1") (pinfunction "GND_1") (pintype "passive"))
      (node (ref "VR2") (pin "1") (pinfunction "GND_1") (pintype "passive"))
      (node (ref "VR3") (pin "1") (pinfunction "GND_1") (pintype "passive"))
    )
    (net (code "48") (name "Net-(BEEP1--)") (class "Default")
      (node (ref "BEEP1") (pin "2") (pinfunction "-_2") (pintype "passive"))
      (node (ref "Q4") (pin "3") (pinfunction "C_3") (pintype "passive"))
    )
    (net (code "49") (name "Net-(BEEP2--)") (class "Default")
      (node (ref "BEEP2") (pin "2") (pinfunction "-_2") (pintype "passive"))
      (node (ref "Q5") (pin "3") (pinfunction "C_3") (pintype "passive"))
    )
    (net (code "50") (name "Net-(D1-PadA)") (class "Default")
      (node (ref "D1") (pin "A") (pinfunction "A_A") (pintype "passive"))
      (node (ref "R1") (pin "1") (pinfunction "1_1") (pintype "passive"))
    )
    (net (code "51") (name "Net-(D2-PadA)") (class "Default")
      (node (ref "D2") (pin "A") (pinfunction "A_A") (pintype "passive"))
      (node (ref "R4") (pin "1") (pinfunction "1_1") (pintype "passive"))
    )
    (net (code "52") (name "Net-(D3-Pad1)") (class "Default")
      (node (ref "D3") (pin "1") (pinfunction "1_1") (pintype "passive"))
      (node (ref "R6") (pin "2") (pinfunction "2_2") (pintype "passive"))
    )
    (net (code "53") (name "Net-(D3-Pad3)") (class "Default")
      (node (ref "D3") (pin "3") (pinfunction "3_3") (pintype "passive"))
      (node (ref "R7") (pin "1") (pinfunction "1_1") (pintype "passive"))
    )
    (net (code "54") (name "Net-(D4-PadA)") (class "Default")
      (node (ref "D4") (pin "A") (pinfunction "A_A") (pintype "passive"))
      (node (ref "R8") (pin "2") (pinfunction "2_2") (pintype "passive"))
    )
    (net (code "55") (name "Net-(P2-RxD)") (class "Default")
      (node (ref "P2") (pin "2") (pinfunction "RxD_2") (pintype "passive"))
      (node (ref "U2") (pin "38") (pinfunction "PC7/I2S3_MCK/TIM8_CH2/SDIO_D7/USART6_RX/DCMI_D1/TIM3_CH2/EVENTOUT_38") (pintype "bidirectional"))
    )
    (net (code "56") (name "Net-(P2-TxD)") (class "Default")
      (node (ref "P2") (pin "3") (pinfunction "TxD_3") (pintype "passive"))
      (node (ref "U2") (pin "37") (pinfunction "PC6/I2S2_MCK/TIM8_CH1/SDIO_D6/USART6_TX/DCMI_D0/TIM3_CH1/EVENTOUT_37") (pintype "bidirectional"))
    )
    (net (code "57") (name "Net-(P4-SCL)") (class "Default")
      (node (ref "P4") (pin "3") (pinfunction "SCL_3") (pintype "passive"))
      (node (ref "P5") (pin "3") (pinfunction "SCL_3") (pintype "passive"))
      (node (ref "R19") (pin "2") (pinfunction "2_2") (pintype "passive"))
    )
    (net (code "58") (name "Net-(P4-SDA)") (class "Default")
      (node (ref "P4") (pin "4") (pinfunction "SDA_4") (pintype "passive"))
      (node (ref "P5") (pin "4") (pinfunction "SDA_4") (pintype "passive"))
      (node (ref "R20") (pin "2") (pinfunction "2_2") (pintype "passive"))
    )
    (net (code "59") (name "Net-(PLD-Pad2)") (class "Default")
      (node (ref "PLD") (pin "2") (pinfunction "2_2") (pintype "passive"))
      (node (ref "PLU") (pin "3") (pinfunction "3_3") (pintype "passive"))
    )
    (net (code "60") (name "Net-(PLD-Pad3)") (class "Default")
      (node (ref "PLD") (pin "3") (pinfunction "3_3") (pintype "passive"))
      (node (ref "PLL") (pin "2") (pinfunction "2_2") (pintype "passive"))
    )
    (net (code "61") (name "Net-(PLL-Pad3)") (class "Default")
      (node (ref "PLL") (pin "3") (pinfunction "3_3") (pintype "passive"))
      (node (ref "PLR") (pin "2") (pinfunction "2_2") (pintype "passive"))
    )
    (net (code "62") (name "Net-(PRD-Pad2)") (class "Default")
      (node (ref "PRD") (pin "2") (pinfunction "2_2") (pintype "passive"))
      (node (ref "PRU") (pin "3") (pinfunction "3_3") (pintype "passive"))
    )
    (net (code "63") (name "Net-(PRD-Pad3)") (class "Default")
      (node (ref "PRD") (pin "3") (pinfunction "3_3") (pintype "passive"))
      (node (ref "PRL") (pin "2") (pinfunction "2_2") (pintype "passive"))
    )
    (net (code "64") (name "Net-(PRL-Pad3)") (class "Default")
      (node (ref "PRL") (pin "3") (pinfunction "3_3") (pintype "passive"))
      (node (ref "PRR") (pin "2") (pinfunction "2_2") (pintype "passive"))
    )
    (net (code "65") (name "Net-(Q1-G)") (class "Default")
      (node (ref "Q1") (pin "1") (pinfunction "G_1") (pintype "passive"))
      (node (ref "Q3") (pin "1") (pinfunction "G_1") (pintype "passive"))
      (node (ref "S1") (pin "2") (pinfunction "2_2") (pintype "passive"))
    )
    (net (code "66") (name "Net-(Q2-G)") (class "Default")
      (node (ref "Q2") (pin "1") (pinfunction "G_1") (pintype "passive"))
      (node (ref "Q3") (pin "3") (pinfunction "D_3") (pintype "passive"))
      (node (ref "R2") (pin "2") (pinfunction "2_2") (pintype "passive"))
    )
    (net (code "67") (name "Net-(Q4-B)") (class "Default")
      (node (ref "Q4") (pin "1") (pinfunction "B_1") (pintype "passive"))
      (node (ref "R34") (pin "2") (pinfunction "2_2") (pintype "passive"))
    )
    (net (code "68") (name "Net-(Q5-B)") (class "Default")
      (node (ref "Q5") (pin "1") (pinfunction "B_1") (pintype "passive"))
      (node (ref "R35") (pin "2") (pinfunction "2_2") (pintype "passive"))
    )
    (net (code "69") (name "Net-(U1-IN+)") (class "Default")
      (node (ref "R3") (pin "1") (pinfunction "1_1") (pintype "passive"))
      (node (ref "R5") (pin "2") (pinfunction "2_2") (pintype "passive"))
      (node (ref "U1") (pin "1") (pinfunction "IN+_1") (pintype "input"))
    )
    (net (code "70") (name "Net-(U2B-PC14-OSC32_IN(PC14){slash}EVENTOUT{slash}OSC32_IN)") (class "Default")
      (node (ref "C15") (pin "1") (pinfunction "1_1") (pintype "passive"))
      (node (ref "U2") (pin "3") (pinfunction "PC14-OSC32_IN(PC14)/EVENTOUT/OSC32_IN_3") (pintype "bidirectional"))
      (node (ref "Y2") (pin "2") (pinfunction "OSC2_2") (pintype "passive"))
    )
    (net (code "71") (name "Net-(U2B-PC15-OSC32_OUT(PC15){slash}EVENTOUT{slash}OSC32_OUT)") (class "Default")
      (node (ref "C19") (pin "1") (pinfunction "1_1") (pintype "passive"))
      (node (ref "U2") (pin "4") (pinfunction "PC15-OSC32_OUT(PC15)/EVENTOUT/OSC32_OUT_4") (pintype "bidirectional"))
      (node (ref "Y2") (pin "1") (pinfunction "OSC1_1") (pintype "passive"))
    )
    (net (code "72") (name "Net-(U2C-PH0-OSC_IN(PH0){slash}EVENTOUT{slash}OSC_IN)") (class "Default")
      (node (ref "C13") (pin "1") (pinfunction "1_1") (pintype "passive"))
      (node (ref "U2") (pin "5") (pinfunction "PH0-OSC_IN(PH0)/EVENTOUT/OSC_IN_5") (pintype "bidirectional"))
      (node (ref "Y1") (pin "2") (pinfunction "OSC2_2") (pintype "passive"))
    )
    (net (code "73") (name "Net-(U2C-PH1-OSC_OUT(PH1){slash}EVENTOUT{slash}OSC_OUT)") (class "Default")
      (node (ref "C17") (pin "1") (pinfunction "1_1") (pintype "passive"))
      (node (ref "U2") (pin "6") (pinfunction "PH1-OSC_OUT(PH1)/EVENTOUT/OSC_OUT_6") (pintype "bidirectional"))
      (node (ref "Y1") (pin "1") (pinfunction "OSC1_1") (pintype "passive"))
    )
    (net (code "74") (name "Net-(U2C-VCAP_1)") (class "Default")
      (node (ref "C14") (pin "2") (pinfunction "2_2") (pintype "passive"))
      (node (ref "U2") (pin "31") (pinfunction "VCAP_1_31") (pintype "power_in"))
    )
    (net (code "75") (name "Net-(U2C-VCAP_2)") (class "Default")
      (node (ref "C18") (pin "2") (pinfunction "2_2") (pintype "passive"))
      (node (ref "U2") (pin "47") (pinfunction "VCAP_2_47") (pintype "power_in"))
    )
    (net (code "76") (name "Net-(U2D-VBAT)") (class "Default")
      (node (ref "C7") (pin "2") (pinfunction "2_2") (pintype "passive"))
      (node (ref "C9") (pin "1") (pinfunction "1_1") (pintype "passive"))
      (node (ref "U2") (pin "1") (pinfunction "VBAT_1") (pintype "power_in"))
      (node (ref "VR3") (pin "2") (pinfunction "Vout_2") (pintype "passive"))
    )
    (net (code "77") (name "Net-(U3-PROG)") (class "Default")
      (node (ref "R9") (pin "2") (pinfunction "2_2") (pintype "passive"))
      (node (ref "U3") (pin "2") (pinfunction "PROG_2") (pintype "passive"))
    )
    (net (code "78") (name "Net-(U4-CLK)") (class "Default")
      (node (ref "R17") (pin "1") (pinfunction "1_1") (pintype "passive"))
      (node (ref "U4") (pin "6") (pinfunction "CLK_6") (pintype "passive"))
    )
    (net (code "79") (name "Net-(U4-DI)") (class "Default")
      (node (ref "R18") (pin "1") (pinfunction "1_1") (pintype "passive"))
      (node (ref "U4") (pin "5") (pinfunction "DI_5") (pintype "passive"))
    )
    (net (code "80") (name "Net-(U4-DO)") (class "Default")
      (node (ref "R16") (pin "2") (pinfunction "2_2") (pintype "passive"))
      (node (ref "U4") (pin "2") (pinfunction "DO_2") (pintype "passive"))
    )
    (net (code "81") (name "Net-(USB1-D+)") (class "Default")
      (node (ref "R11") (pin "1") (pinfunction "1_1") (pintype "passive"))
      (node (ref "USB1") (pin "3") (pinfunction "D+_3") (pintype "passive"))
    )
    (net (code "82") (name "Net-(USB1-D-)") (class "Default")
      (node (ref "R13") (pin "1") (pinfunction "1_1") (pintype "passive"))
      (node (ref "USB1") (pin "2") (pinfunction "D-_2") (pintype "passive"))
    )
    (net (code "83") (name "Net-(USB2-D+)") (class "Default")
      (node (ref "R12") (pin "1") (pinfunction "1_1") (pintype "passive"))
      (node (ref "USB2") (pin "3") (pinfunction "D+_3") (pintype "passive"))
    )
    (net (code "84") (name "Net-(USB2-D-)") (class "Default")
      (node (ref "R14") (pin "1") (pinfunction "1_1") (pintype "passive"))
      (node (ref "USB2") (pin "2") (pinfunction "D-_2") (pintype "passive"))
    )
    (net (code "85") (name "Net-(USB2-ID)") (class "Default")
      (node (ref "R10") (pin "1") (pinfunction "1_1") (pintype "passive"))
      (node (ref "USB2") (pin "4") (pinfunction "ID_4") (pintype "passive"))
    )
    (net (code "86") (name "USB_5V") (class "Default")
      (node (ref "C10") (pin "2") (pinfunction "2_2") (pintype "passive"))
      (node (ref "Q2") (pin "2") (pinfunction "S_2") (pintype "passive"))
      (node (ref "R2") (pin "1") (pinfunction "1_1") (pintype "passive"))
      (node (ref "R8") (pin "1") (pinfunction "1_1") (pintype "passive"))
      (node (ref "S1") (pin "1") (pinfunction "1_1") (pintype "passive"))
      (node (ref "U3") (pin "4") (pinfunction "VCC_4") (pintype "passive"))
      (node (ref "USB1") (pin "1") (pinfunction "+5V_1") (pintype "passive"))
      (node (ref "USB2") (pin "1") (pinfunction "+5V_1") (pintype "passive"))
    )
    (net (code "87") (name "VBAT") (class "Default")
      (node (ref "C12") (pin "1") (pinfunction "1_1") (pintype "passive"))
      (node (ref "C8") (pin "2") (pinfunction "2_2") (pintype "passive"))
      (node (ref "P1") (pin "2") (pinfunction "B+_2") (pintype "passive"))
      (node (ref "Q1") (pin "2") (pinfunction "S_2") (pintype "passive"))
      (node (ref "U3") (pin "5") (pinfunction "BAT_5") (pintype "passive"))
      (node (ref "VR3") (pin "3") (pinfunction "Vin_3") (pintype "passive"))
    )
    (net (code "88") (name "VCC") (class "Default")
      (node (ref "C1") (pin "2") (pinfunction "2_2") (pintype "passive"))
      (node (ref "C11") (pin "2") (pinfunction "2_2") (pintype "passive"))
      (node (ref "C3") (pin "1") (pinfunction "1_1") (pintype "passive"))
      (node (ref "D3") (pin "2") (pinfunction "2_2") (pintype "passive"))
      (node (ref "J1") (pin "4") (pinfunction "VDD_4") (pintype "passive"))
      (node (ref "P3") (pin "5") (pinfunction "VCC_5") (pintype "passive"))
      (node (ref "R15") (pin "2") (pinfunction "2_2") (pintype "passive"))
      (node (ref "U2") (pin "13") (pinfunction "VDDA_13") (pintype "power_in"))
      (node (ref "U2") (pin "19") (pinfunction "VDD_19") (pintype "power_in"))
      (node (ref "U2") (pin "32") (pinfunction "VDD_32") (pintype "power_in"))
      (node (ref "U2") (pin "48") (pinfunction "VDD_48") (pintype "power_in"))
      (node (ref "U2") (pin "64") (pinfunction "VDD_64") (pintype "power_in"))
      (node (ref "U4") (pin "3") (pinfunction "~{WP}_3") (pintype "passive"))
      (node (ref "U4") (pin "7") (pinfunction "~{HOLD}_ro_~{RESET}_7") (pintype "passive"))
      (node (ref "U4") (pin "8") (pinfunction "VCC_8") (pintype "passive"))
      (node (ref "U5") (pin "8") (pinfunction "VCC_8") (pintype "passive"))
      (node (ref "VR1") (pin "2") (pinfunction "Vout_2") (pintype "passive"))
    )
    (net (code "89") (name "VEX") (class "Default")
      (node (ref "BEEP1") (pin "1") (pinfunction "+_1") (pintype "passive"))
      (node (ref "BEEP2") (pin "1") (pinfunction "+_1") (pintype "passive"))
      (node (ref "C4") (pin "2") (pinfunction "2_2") (pintype "passive"))
      (node (ref "C6") (pin "1") (pinfunction "1_1") (pintype "passive"))
      (node (ref "P4") (pin "2") (pinfunction "VCC_2") (pintype "passive"))
      (node (ref "P5") (pin "2") (pinfunction "VCC_2") (pintype "passive"))
      (node (ref "VR2") (pin "2") (pinfunction "Vout_2") (pintype "passive"))
    )
    (net (code "90") (name "VIN") (class "Default")
      (node (ref "C2") (pin "2") (pinfunction "2_2") (pintype "passive"))
      (node (ref "C5") (pin "2") (pinfunction "2_2") (pintype "passive"))
      (node (ref "Q1") (pin "3") (pinfunction "D_3") (pintype "passive"))
      (node (ref "Q2") (pin "3") (pinfunction "D_3") (pintype "passive"))
      (node (ref "R3") (pin "2") (pinfunction "2_2") (pintype "passive"))
      (node (ref "U1") (pin "5") (pinfunction "V+_5") (pintype "power_in"))
      (node (ref "VR1") (pin "3") (pinfunction "Vin_3") (pintype "passive"))
      (node (ref "VR2") (pin "3") (pinfunction "Vin_3") (pintype "passive"))
    )
    (net (code "91") (name "unconnected-(P3-ENB-Pad6)") (class "Default")
      (node (ref "P3") (pin "6") (pinfunction "ENB_6") (pintype "passive"))
    )
    (net (code "92") (name "unconnected-(PLD-Pad1)") (class "Default")
      (node (ref "PLD") (pin "1") (pinfunction "1_1") (pintype "passive"))
    )
    (net (code "93") (name "unconnected-(PLL-Pad1)") (class "Default")
      (node (ref "PLL") (pin "1") (pinfunction "1_1") (pintype "passive"))
    )
    (net (code "94") (name "unconnected-(PLR-Pad1)") (class "Default")
      (node (ref "PLR") (pin "1") (pinfunction "1_1") (pintype "passive"))
    )
    (net (code "95") (name "unconnected-(PLR-Pad3)") (class "Default")
      (node (ref "PLR") (pin "3") (pinfunction "3_3") (pintype "passive"))
    )
    (net (code "96") (name "unconnected-(PLU-Pad1)") (class "Default")
      (node (ref "PLU") (pin "1") (pinfunction "1_1") (pintype "passive"))
    )
    (net (code "97") (name "unconnected-(PRD-Pad1)") (class "Default")
      (node (ref "PRD") (pin "1") (pinfunction "1_1") (pintype "passive"))
    )
    (net (code "98") (name "unconnected-(PRL-Pad1)") (class "Default")
      (node (ref "PRL") (pin "1") (pinfunction "1_1") (pintype "passive"))
    )
    (net (code "99") (name "unconnected-(PRR-Pad1)") (class "Default")
      (node (ref "PRR") (pin "1") (pinfunction "1_1") (pintype "passive"))
    )
    (net (code "100") (name "unconnected-(PRR-Pad3)") (class "Default")
      (node (ref "PRR") (pin "3") (pinfunction "3_3") (pintype "passive"))
    )
    (net (code "101") (name "unconnected-(PRU-Pad1)") (class "Default")
      (node (ref "PRU") (pin "1") (pinfunction "1_1") (pintype "passive"))
    )
  )
)
